# led.net
KiCad netlist of a schematic drawn in EAGLE
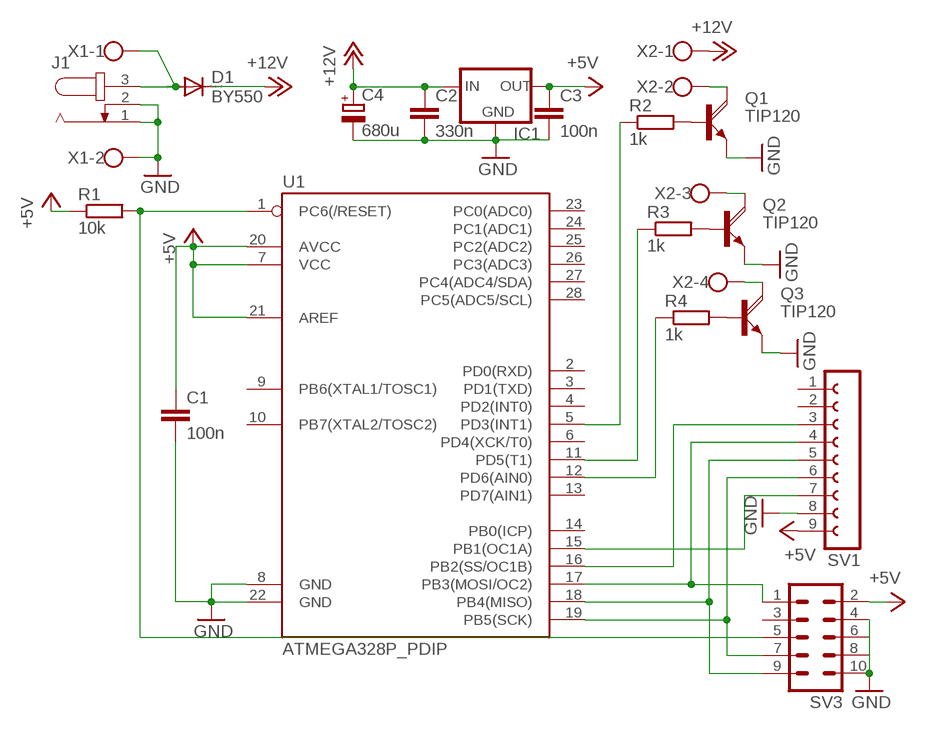
[diagram p0: schematic, sheet 1]

(export (version "E")
  (design (tool "Eeschema 10.0.6"))
  (components
    (comp (ref "C1")
      (value "100n")
      (footprint "eagle-import:C050-024X044")
      (libsource (lib "eagle-import") (part "C-EU050-024X044"))
    )
    (comp (ref "C2")
      (value "330n")
      (footprint "eagle-import:C050-024X044")
      (libsource (lib "eagle-import") (part "C-EU050-024X044"))
    )
    (comp (ref "C3")
      (value "100n")
      (footprint "eagle-import:C050-024X044")
      (libsource (lib "eagle-import") (part "C-EU050-024X044"))
    )
    (comp (ref "C4")
      (value "680u")
      (footprint "eagle-import:E5-10,5")
      (libsource (lib "eagle-import") (part "CPOL-EUE5-10.5"))
    )
    (comp (ref "D1")
      (value "BY550")
      (footprint "eagle-import:DO27-15")
      (libsource (lib "eagle-import") (part "BY550"))
    )
    (comp (ref "IC1")
      (value "78XXS")
      (footprint "eagle-import:78XXS")
      (libsource (lib "eagle-import") (part "78XXS"))
    )
    (comp (ref "J1")
      (value "JACK-PLUG1")
      (footprint "eagle-import:SPC4078")
      (libsource (lib "eagle-import") (part "JACK-PLUG1"))
    )
    (comp (ref "Q1")
      (value "TIP120")
      (footprint "eagle-import:TO220AV")
      (libsource (lib "eagle-import") (part "TIP120"))
    )
    (comp (ref "Q2")
      (value "TIP120")
      (footprint "eagle-import:TO220AV")
      (libsource (lib "eagle-import") (part "TIP120"))
    )
    (comp (ref "Q3")
      (value "TIP120")
      (footprint "eagle-import:TO220AV")
      (libsource (lib "eagle-import") (part "TIP120"))
    )
    (comp (ref "R1")
      (value "10k")
      (footprint "eagle-import:0207_10")
      (libsource (lib "eagle-import") (part "resistor_R-EU_0207/10"))
    )
    (comp (ref "R2")
      (value "1k")
      (footprint "eagle-import:0207_10")
      (libsource (lib "eagle-import") (part "R-EU_0207/10"))
    )
    (comp (ref "R3")
      (value "1k")
      (footprint "eagle-import:0207_10")
      (libsource (lib "eagle-import") (part "R-EU_0207/10"))
    )
    (comp (ref "R4")
      (value "1k")
      (footprint "eagle-import:0207_10")
      (libsource (lib "eagle-import") (part "R-EU_0207/10"))
    )
    (comp (ref "SV1")
      (value "FE09-1")
      (footprint "eagle-import:FE09")
      (libsource (lib "eagle-import") (part "FE09-1"))
    )
    (comp (ref "SV3")
      (value "MA05-2")
      (footprint "eagle-import:MA05-2")
      (libsource (lib "eagle-import") (part "MA05-2"))
    )
    (comp (ref "U1")
      (value "ATMEGA328P_PDIP")
      (footprint "eagle-import:DIL28-3")
      (libsource (lib "eagle-import") (part "ATMEGA328P_PDIP"))
    )
    (comp (ref "X1")
      (value "W237-102")
      (footprint "eagle-import:W237-102")
      (fields (field (name "MPN") "237-102"))
      (libsource (lib "eagle-import") (part "W237-102"))
    )
    (comp (ref "X2")
      (value "W237-4")
      (footprint "eagle-import:W237-4")
      (libsource (lib "eagle-import") (part "W237-4"))
    )
  )
  (nets
    (net (code "1") (name "+5V") (class "Default")
      (node (ref "C1") (pin "1") (pinfunction "1_1") (pintype "passive"))
      (node (ref "C3") (pin "1") (pinfunction "1_1") (pintype "passive"))
      (node (ref "IC1") (pin "OUT") (pinfunction "OUT_OUT") (pintype "passive"))
      (node (ref "R1") (pin "1") (pinfunction "1_1") (pintype "passive"))
      (node (ref "SV1") (pin "9") (pinfunction "9_9") (pintype "passive"))
      (node (ref "SV3") (pin "2") (pinfunction "2_2") (pintype "passive"))
      (node (ref "U1") (pin "20") (pinfunction "AVCC_20") (pintype "bidirectional"))
      (node (ref "U1") (pin "21") (pinfunction "AREF_21") (pintype "bidirectional"))
      (node (ref "U1") (pin "7") (pinfunction "VCC_7") (pintype "bidirectional"))
    )
    (net (code "2") (name "+12V") (class "Default")
      (node (ref "C2") (pin "1") (pinfunction "1_1") (pintype "passive"))
      (node (ref "C4") (pin "+") (pinfunction "+_+") (pintype "passive"))
      (node (ref "D1") (pin "C") (pinfunction "C_C") (pintype "passive"))
      (node (ref "IC1") (pin "IN") (pinfunction "IN_IN") (pintype "input"))
      (node (ref "X2") (pin "1") (pinfunction "KL_1") (pintype "passive"))
    )
    (net (code "3") (name "GND") (class "Default")
      (node (ref "C1") (pin "2") (pinfunction "2_2") (pintype "passive"))
      (node (ref "C2") (pin "2") (pinfunction "2_2") (pintype "passive"))
      (node (ref "C3") (pin "2") (pinfunction "2_2") (pintype "passive"))
      (node (ref "C4") (pin "-") (pinfunction "-_-") (pintype "passive"))
      (node (ref "IC1") (pin "GND") (pinfunction "GND_GND") (pintype "input"))
      (node (ref "J1") (pin "1") (pinfunction "1_1") (pintype "passive"))
      (node (ref "J1") (pin "2") (pinfunction "2_2") (pintype "passive"))
      (node (ref "Q1") (pin "E") (pinfunction "E_E") (pintype "passive"))
      (node (ref "Q2") (pin "E") (pinfunction "E_E") (pintype "passive"))
      (node (ref "Q3") (pin "E") (pinfunction "E_E") (pintype "passive"))
      (node (ref "SV1") (pin "8") (pinfunction "8_8") (pintype "passive"))
      (node (ref "SV3") (pin "10") (pinfunction "10_10") (pintype "passive"))
      (node (ref "SV3") (pin "4") (pinfunction "4_4") (pintype "passive"))
      (node (ref "U1") (pin "22") (pinfunction "GND_22") (pintype "bidirectional"))
      (node (ref "U1") (pin "8") (pinfunction "GND_8") (pintype "bidirectional"))
      (node (ref "X1") (pin "2") (pinfunction "KL_2") (pintype "passive"))
    )
    (net (code "4") (name "Net-(Q1-PadB)") (class "Default")
      (node (ref "Q1") (pin "B") (pinfunction "B_B") (pintype "passive"))
      (node (ref "R2") (pin "2") (pinfunction "2_2") (pintype "passive"))
    )
    (net (code "5") (name "Net-(Q2-PadB)") (class "Default")
      (node (ref "Q2") (pin "B") (pinfunction "B_B") (pintype "passive"))
      (node (ref "R3") (pin "2") (pinfunction "2_2") (pintype "passive"))
    )
    (net (code "6") (name "Net-(Q3-PadB)") (class "Default")
      (node (ref "Q3") (pin "B") (pinfunction "B_B") (pintype "passive"))
      (node (ref "R4") (pin "2") (pinfunction "2_2") (pintype "passive"))
    )
    (net (code "7") (name "Net-(U1-PB1(OC1A))") (class "Default")
      (node (ref "SV1") (pin "7") (pinfunction "7_7") (pintype "passive"))
      (node (ref "U1") (pin "15") (pinfunction "PB1(OC1A)_15") (pintype "bidirectional"))
    )
    (net (code "8") (name "Net-(U1-PB2(SS{slash}OC1B))") (class "Default")
      (node (ref "SV1") (pin "3") (pinfunction "3_3") (pintype "passive"))
      (node (ref "U1") (pin "16") (pinfunction "PB2(SS/OC1B)_16") (pintype "bidirectional"))
    )
    (net (code "9") (name "Net-(U1-PB3(MOSI{slash}OC2))") (class "Default")
      (node (ref "SV1") (pin "4") (pinfunction "4_4") (pintype "passive"))
      (node (ref "SV3") (pin "1") (pinfunction "1_1") (pintype "passive"))
      (node (ref "U1") (pin "17") (pinfunction "PB3(MOSI/OC2)_17") (pintype "bidirectional"))
    )
    (net (code "10") (name "Net-(U1-PB4(MISO))") (class "Default")
      (node (ref "SV1") (pin "5") (pinfunction "5_5") (pintype "passive"))
      (node (ref "SV3") (pin "9") (pinfunction "9_9") (pintype "passive"))
      (node (ref "U1") (pin "18") (pinfunction "PB4(MISO)_18") (pintype "bidirectional"))
    )
    (net (code "11") (name "Net-(U1-PB5(SCK))") (class "Default")
      (node (ref "SV1") (pin "6") (pinfunction "6_6") (pintype "passive"))
      (node (ref "SV3") (pin "7") (pinfunction "7_7") (pintype "passive"))
      (node (ref "U1") (pin "19") (pinfunction "PB5(SCK)_19") (pintype "bidirectional"))
    )
    (net (code "12") (name "Net-(U1-PC6({slash}RESET))") (class "Default")
      (node (ref "R1") (pin "2") (pinfunction "2_2") (pintype "passive"))
      (node (ref "SV3") (pin "5") (pinfunction "5_5") (pintype "passive"))
      (node (ref "U1") (pin "1") (pinfunction "PC6(/RESET)_1") (pintype "bidirectional"))
    )
    (net (code "13") (name "Net-(U1-PD3(INT1))") (class "Default")
      (node (ref "R2") (pin "1") (pinfunction "1_1") (pintype "passive"))
      (node (ref "U1") (pin "5") (pinfunction "PD3(INT1)_5") (pintype "bidirectional"))
    )
    (net (code "14") (name "Net-(U1-PD5(T1))") (class "Default")
      (node (ref "R3") (pin "1") (pinfunction "1_1") (pintype "passive"))
      (node (ref "U1") (pin "11") (pinfunction "PD5(T1)_11") (pintype "bidirectional"))
    )
    (net (code "15") (name "Net-(U1-PD6(AIN0))") (class "Default")
      (node (ref "R4") (pin "1") (pinfunction "1_1") (pintype "passive"))
      (node (ref "U1") (pin "12") (pinfunction "PD6(AIN0)_12") (pintype "bidirectional"))
    )
    (net (code "16") (name "Net-(X1A-KL)") (class "Default")
      (node (ref "D1") (pin "A") (pinfunction "A_A") (pintype "passive"))
      (node (ref "J1") (pin "3") (pinfunction "3_3") (pintype "passive"))
      (node (ref "X1") (pin "1") (pinfunction "KL_1") (pintype "passive"))
    )
    (net (code "17") (name "Net-(X2B-KL)") (class "Default")
      (node (ref "Q1") (pin "C") (pinfunction "C_C") (pintype "passive"))
      (node (ref "X2") (pin "2") (pinfunction "KL_2") (pintype "passive"))
    )
    (net (code "18") (name "Net-(X2C-KL)") (class "Default")
      (node (ref "Q2") (pin "C") (pinfunction "C_C") (pintype "passive"))
      (node (ref "X2") (pin "3") (pinfunction "KL_3") (pintype "passive"))
    )
    (net (code "19") (name "Net-(X2D-KL)") (class "Default")
      (node (ref "Q3") (pin "C") (pinfunction "C_C") (pintype "passive"))
      (node (ref "X2") (pin "4") (pinfunction "KL_4") (pintype "passive"))
    )
    (net (code "20") (name "unconnected-(SV1-Pad1)") (class "Default")
      (node (ref "SV1") (pin "1") (pinfunction "1_1") (pintype "passive"))
    )
    (net (code "21") (name "unconnected-(SV1-Pad2)") (class "Default")
      (node (ref "SV1") (pin "2") (pinfunction "2_2") (pintype "passive"))
    )
    (net (code "22") (name "unconnected-(SV3-Pad3)") (class "Default")
      (node (ref "SV3") (pin "3") (pinfunction "3_3") (pintype "passive"))
    )
    (net (code "23") (name "unconnected-(SV3-Pad6)") (class "Default")
      (node (ref "SV3") (pin "6") (pinfunction "6_6") (pintype "passive"))
    )
    (net (code "24") (name "unconnected-(SV3-Pad8)") (class "Default")
      (node (ref "SV3") (pin "8") (pinfunction "8_8") (pintype "passive"))
    )
    (net (code "25") (name "unconnected-(U1-PB0(ICP)-Pad14)") (class "Default")
      (node (ref "U1") (pin "14") (pinfunction "PB0(ICP)_14") (pintype "bidirectional"))
    )
    (net (code "26") (name "unconnected-(U1-PB6(XTAL1{slash}TOSC1)-Pad9)") (class "Default")
      (node (ref "U1") (pin "9") (pinfunction "PB6(XTAL1/TOSC1)_9") (pintype "bidirectional"))
    )
    (net (code "27") (name "unconnected-(U1-PB7(XTAL2{slash}TOSC2)-Pad10)") (class "Default")
      (node (ref "U1") (pin "10") (pinfunction "PB7(XTAL2/TOSC2)_10") (pintype "bidirectional"))
    )
    (net (code "28") (name "unconnected-(U1-PC0(ADC0)-Pad23)") (class "Default")
      (node (ref "U1") (pin "23") (pinfunction "PC0(ADC0)_23") (pintype "bidirectional"))
    )
    (net (code "29") (name "unconnected-(U1-PC1(ADC1)-Pad24)") (class "Default")
      (node (ref "U1") (pin "24") (pinfunction "PC1(ADC1)_24") (pintype "bidirectional"))
    )
    (net (code "30") (name "unconnected-(U1-PC2(ADC2)-Pad25)") (class "Default")
      (node (ref "U1") (pin "25") (pinfunction "PC2(ADC2)_25") (pintype "bidirectional"))
    )
    (net (code "31") (name "unconnected-(U1-PC3(ADC3)-Pad26)") (class "Default")
      (node (ref "U1") (pin "26") (pinfunction "PC3(ADC3)_26") (pintype "bidirectional"))
    )
    (net (code "32") (name "unconnected-(U1-PC4(ADC4{slash}SDA)-Pad27)") (class "Default")
      (node (ref "U1") (pin "27") (pinfunction "PC4(ADC4/SDA)_27") (pintype "bidirectional"))
    )
    (net (code "33") (name "unconnected-(U1-PC5(ADC5{slash}SCL)-Pad28)") (class "Default")
      (node (ref "U1") (pin "28") (pinfunction "PC5(ADC5/SCL)_28") (pintype "bidirectional"))
    )
    (net (code "34") (name "unconnected-(U1-PD0(RXD)-Pad2)") (class "Default")
      (node (ref "U1") (pin "2") (pinfunction "PD0(RXD)_2") (pintype "bidirectional"))
    )
    (net (code "35") (name "unconnected-(U1-PD1(TXD)-Pad3)") (class "Default")
      (node (ref "U1") (pin "3") (pinfunction "PD1(TXD)_3") (pintype "bidirectional"))
    )
    (net (code "36") (name "unconnected-(U1-PD2(INT0)-Pad4)") (class "Default")
      (node (ref "U1") (pin "4") (pinfunction "PD2(INT0)_4") (pintype "bidirectional"))
    )
    (net (code "37") (name "unconnected-(U1-PD4(XCK{slash}T0)-Pad6)") (class "Default")
      (node (ref "U1") (pin "6") (pinfunction "PD4(XCK/T0)_6") (pintype "bidirectional"))
    )
    (net (code "38") (name "unconnected-(U1-PD7(AIN1)-Pad13)") (class "Default")
      (node (ref "U1") (pin "13") (pinfunction "PD7(AIN1)_13") (pintype "bidirectional"))
    )
  )
)
